# um982.net
KiCad netlist of a schematic drawn in Altium Designer
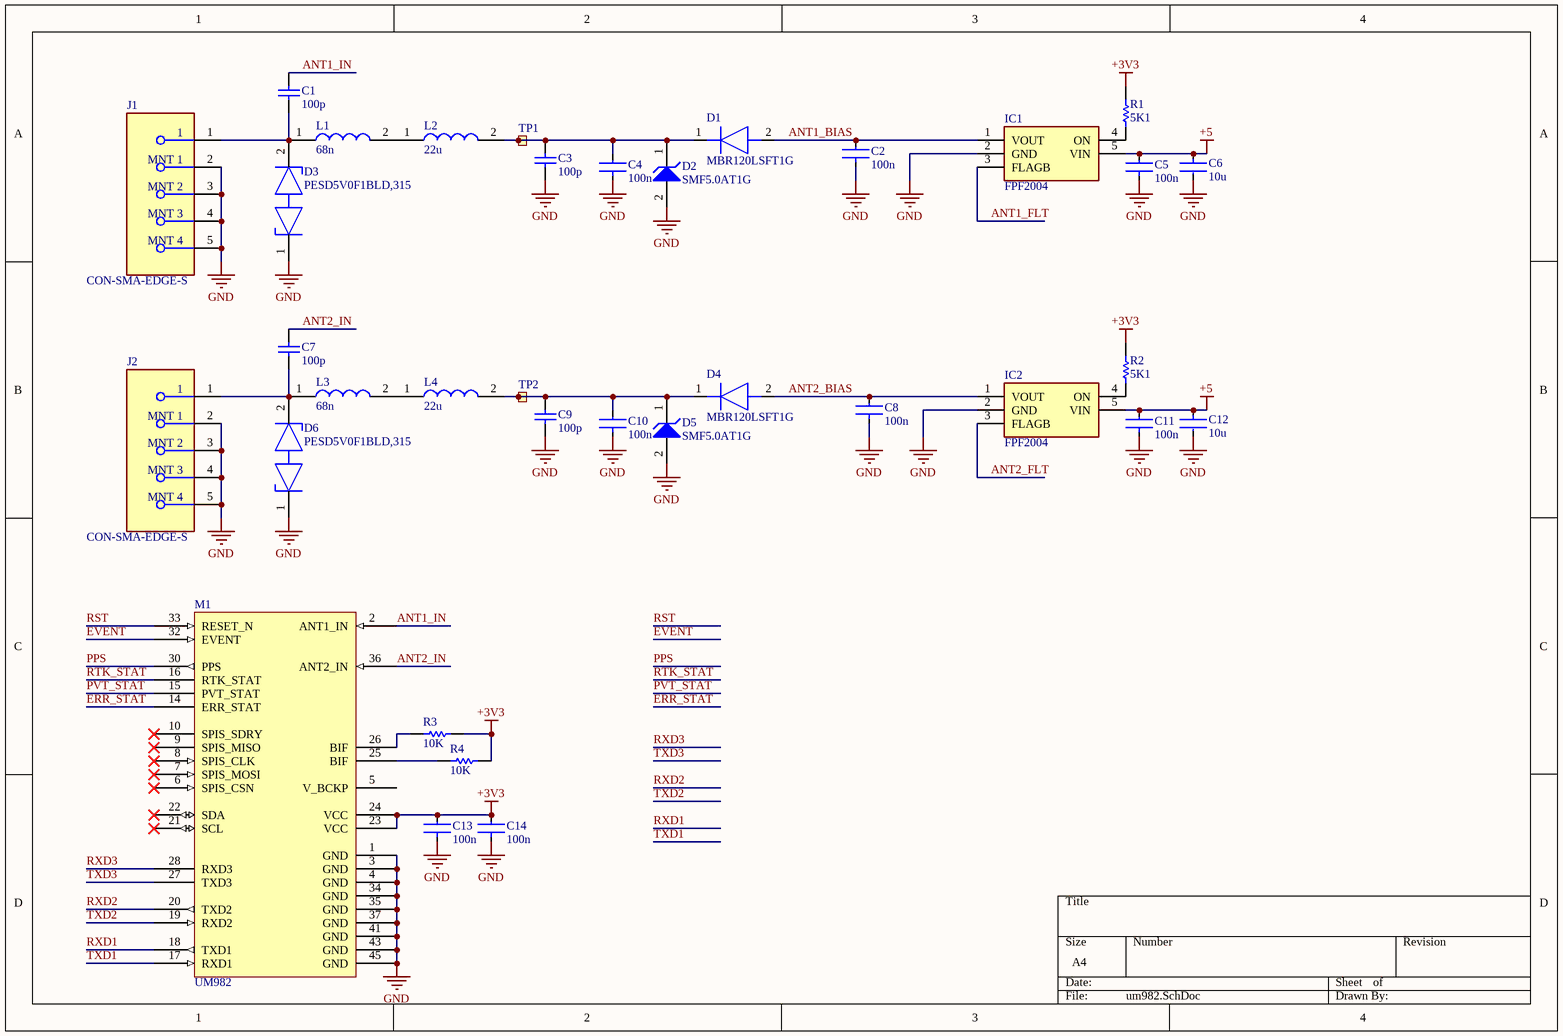
[diagram p0: um982.SchDoc]

(export (version "E")
  (design (tool "Eeschema 10.0.6"))
  (components
    (comp (ref "C1")
      (value "100p")
      (footprint "CAPC1005X55X25ML05T10")
      (fields (field (name "MANUFACTURER") "Murata") (field (name "PART NUMBER") "GRM1555C1H101JA01D"))
      (libsource (lib "Altium Content Vault") (part "CAP"))
    )
    (comp (ref "C2")
      (value "100n")
      (footprint "FP-C1005-050-0_05-IPC_C")
      (description "Multilayer Ceramic Capacitors 100nF ±10% 50V X7R SMD 0402")
      (fields (field (name "VOLTAGE") "50V") (field (name "TOLERANCE") "10%"))
      (libsource (lib "Altium Content Vault") (part "b4654b650e69147ec39a6b967a45e02"))
    )
    (comp (ref "C3")
      (value "100p")
      (footprint "CAPC1005X55X25ML05T10")
      (fields (field (name "MANUFACTURER") "Murata") (field (name "PART NUMBER") "GRM1555C1H101JA01D"))
      (libsource (lib "Altium Content Vault") (part "CAP"))
    )
    (comp (ref "C4")
      (value "100n")
      (footprint "FP-C1005-050-0_05-IPC_A")
      (description "Multilayer Ceramic Capacitors 100nF ±10% 50V X7R SMD 0402")
      (fields (field (name "VOLTAGE") "50V") (field (name "TOLERANCE") "10%"))
      (libsource (lib "Altium Content Vault") (part "b4654b650e69147ec39a6b967a45e02"))
    )
    (comp (ref "C5")
      (value "100n")
      (footprint "FP-C1005-050-0_05-IPC_C")
      (description "Multilayer Ceramic Capacitors 100nF ±10% 50V X7R SMD 0402")
      (fields (field (name "VOLTAGE") "50V") (field (name "TOLERANCE") "10%"))
      (libsource (lib "Altium Content Vault") (part "b4654b650e69147ec39a6b967a45e02"))
    )
    (comp (ref "C6")
      (value "10u")
      (footprint "FP-C1608-080-IPC_A")
      (description "CAP CER 10UF 25V X5R 0603")
      (fields (field (name "TOLERANCE") "20%") (field (name "Comment") "C1608X5R1E106M080AC"))
      (libsource (lib "Altium Content Vault") (part "11868f565c42a9108669ba33697ecf6"))
    )
    (comp (ref "C7")
      (value "100p")
      (footprint "CAPC1005X55X25ML05T10")
      (fields (field (name "MANUFACTURER") "Murata") (field (name "PART NUMBER") "GRM1555C1H101JA01D"))
      (libsource (lib "Altium Content Vault") (part "CAP"))
    )
    (comp (ref "C8")
      (value "100n")
      (footprint "FP-C1005-050-0_05-IPC_C")
      (description "Multilayer Ceramic Capacitors 100nF ±10% 50V X7R SMD 0402")
      (fields (field (name "VOLTAGE") "50V") (field (name "TOLERANCE") "10%"))
      (libsource (lib "Altium Content Vault") (part "b4654b650e69147ec39a6b967a45e02"))
    )
    (comp (ref "C9")
      (value "100p")
      (footprint "CAPC1005X55X25ML05T10")
      (fields (field (name "MANUFACTURER") "Murata") (field (name "PART NUMBER") "GRM1555C1H101JA01D"))
      (libsource (lib "Altium Content Vault") (part "CAP"))
    )
    (comp (ref "C10")
      (value "100n")
      (footprint "FP-C1005-050-0_05-IPC_A")
      (description "Multilayer Ceramic Capacitors 100nF ±10% 50V X7R SMD 0402")
      (fields (field (name "VOLTAGE") "50V") (field (name "TOLERANCE") "10%"))
      (libsource (lib "Altium Content Vault") (part "b4654b650e69147ec39a6b967a45e02"))
    )
    (comp (ref "C11")
      (value "100n")
      (footprint "FP-C1005-050-0_05-IPC_C")
      (description "Multilayer Ceramic Capacitors 100nF ±10% 50V X7R SMD 0402")
      (fields (field (name "VOLTAGE") "50V") (field (name "TOLERANCE") "10%"))
      (libsource (lib "Altium Content Vault") (part "b4654b650e69147ec39a6b967a45e02"))
    )
    (comp (ref "C12")
      (value "10u")
      (footprint "FP-C1608-080-IPC_A")
      (description "CAP CER 10UF 25V X5R 0603")
      (fields (field (name "TOLERANCE") "20%") (field (name "Comment") "C1608X5R1E106M080AC"))
      (libsource (lib "Altium Content Vault") (part "11868f565c42a9108669ba33697ecf6"))
    )
    (comp (ref "C13")
      (value "100n")
      (footprint "FP-C1005-050-0_05-IPC_A")
      (description "Multilayer Ceramic Capacitors 100nF ±10% 50V X7R SMD 0402")
      (fields (field (name "VOLTAGE") "50V") (field (name "TOLERANCE") "10%"))
      (libsource (lib "Altium Content Vault") (part "b4654b650e69147ec39a6b967a45e02"))
    )
    (comp (ref "C14")
      (value "100n")
      (footprint "FP-C1005-050-0_05-IPC_A")
      (description "Multilayer Ceramic Capacitors 100nF ±10% 50V X7R SMD 0402")
      (fields (field (name "VOLTAGE") "50V") (field (name "TOLERANCE") "10%"))
      (libsource (lib "Altium Content Vault") (part "b4654b650e69147ec39a6b967a45e02"))
    )
    (comp (ref "D1")
      (value "MBR120LSFT1G")
      (footprint "SamacSys:SODFL3616X98N")
      (description "Diode")
      (fields (field (name "MOUSER PART NUMBER") "863-MBR120LSFT1G"))
      (libsource (lib "*") (part "MBR120LSFT1G"))
    )
    (comp (ref "D2")
      (value "SMF5.0AT1G")
      (footprint "ONSC-SOD-123FL-2-498_V")
      (description "200 W Transient Voltage Suppressor, 2-Pin SOD-123FL, Pb-Free, Tape and Reel")
      (fields (field (name "MANUFACTURER") "On Semiconductor"))
      (libsource (lib "Altium Content Vault") (part "ONSC-K1A2-2"))
    )
    (comp (ref "D3")
      (value "PESD5V0F1BLD,315")
      (footprint "FP-SOD882D-MFG")
      (description "TVS DIODE 5.5V 15V 2DFN1006D")
      (libsource (lib "Altium Content Vault") (part "76a895bf0735dc68486ae99620ec8f1"))
    )
    (comp (ref "D4")
      (value "MBR120LSFT1G")
      (footprint "SamacSys:SODFL3616X98N")
      (description "Diode")
      (fields (field (name "MOUSER PART NUMBER") "863-MBR120LSFT1G"))
      (libsource (lib "*") (part "MBR120LSFT1G"))
    )
    (comp (ref "D5")
      (value "SMF5.0AT1G")
      (footprint "ONSC-SOD-123FL-2-498_V")
      (description "200 W Transient Voltage Suppressor, 2-Pin SOD-123FL, Pb-Free, Tape and Reel")
      (fields (field (name "MANUFACTURER") "On Semiconductor"))
      (libsource (lib "Altium Content Vault") (part "ONSC-K1A2-2"))
    )
    (comp (ref "D6")
      (value "PESD5V0F1BLD,315")
      (footprint "FP-SOD882D-MFG")
      (description "TVS DIODE 5.5V 15V 2DFN1006D")
      (libsource (lib "Altium Content Vault") (part "76a895bf0735dc68486ae99620ec8f1"))
    )
    (comp (ref "IC1")
      (value "FPF2004")
      (footprint "SamacSys:SOT65P210X110-5N")
      (description "Integrated Circuit")
      (fields (field (name "MOUSER PART NUMBER") "512-FPF2004"))
      (libsource (lib "*") (part "FPF2004"))
    )
    (comp (ref "IC2")
      (value "FPF2004")
      (footprint "SamacSys:SOT65P210X110-5N")
      (description "Integrated Circuit")
      (fields (field (name "MOUSER PART NUMBER") "512-FPF2004"))
      (libsource (lib "*") (part "FPF2004"))
    )
    (comp (ref "J1")
      (value "CON-SMA-EDGE-S")
      (footprint "FP-CON-SMA-EDGE-S-MFG")
      (description "CONN SMA JACK STR EDGE MNT")
      (fields
        (field (name "OCTOPART") "https://octopart.com/con-sma-edge-s-rf+solutions-70967450")
        (field (name "MANUFACTURER") "RF Solutions Ltd.")
      )
      (libsource (lib "Altium Content Vault") (part "a163d97a771fcdd2fd1f1a9264c171f"))
    )
    (comp (ref "J2")
      (value "CON-SMA-EDGE-S")
      (footprint "FP-CON-SMA-EDGE-S-MFG")
      (description "CONN SMA JACK STR EDGE MNT")
      (fields
        (field (name "OCTOPART") "https://octopart.com/con-sma-edge-s-rf+solutions-70967450")
        (field (name "MANUFACTURER") "RF Solutions Ltd.")
      )
      (libsource (lib "Altium Content Vault") (part "a163d97a771fcdd2fd1f1a9264c171f"))
    )
    (comp (ref "L1")
      (value "68n")
      (footprint "SamacSys:LQG15WH0N7B02D")
      (description "Inductor")
      (fields
        (field (name "MANUFACTURER_PART_NUMBER") "LQG15HS68NJ02D")
        (field (name "MOUSER PART NUMBER") "81-LQG15HS68NJ02D")
      )
      (libsource (lib "*") (part "LQG15HS68NJ02D"))
    )
    (comp (ref "L2")
      (value "22u")
      (footprint "SamacSys:INDM4532X340N")
      (description "Inductor")
      (fields
        (field (name "MANUFACTURER_PART_NUMBER") "NL453232T-220J-PF")
        (field (name "MOUSER PART NUMBER") "810-NL453232T-220JPF")
      )
      (libsource (lib "*") (part "NL453232T-220J-PF"))
    )
    (comp (ref "L3")
      (value "68n")
      (footprint "SamacSys:LQG15WH0N7B02D")
      (description "Inductor")
      (fields
        (field (name "MANUFACTURER_PART_NUMBER") "LQG15HS68NJ02D")
        (field (name "MOUSER PART NUMBER") "81-LQG15HS68NJ02D")
      )
      (libsource (lib "*") (part "LQG15HS68NJ02D"))
    )
    (comp (ref "L4")
      (value "22u")
      (footprint "SamacSys:INDM4532X340N")
      (description "Inductor")
      (fields
        (field (name "MANUFACTURER_PART_NUMBER") "NL453232T-220J-PF")
        (field (name "MOUSER PART NUMBER") "810-NL453232T-220JPF")
      )
      (libsource (lib "*") (part "NL453232T-220J-PF"))
    )
    (comp (ref "M1")
      (value "UM982")
      (footprint "UM982")
      (description "All-constellation Multi-frequencyHigh Precision Positioning & Heading Module")
      (libsource (lib "UM982") (part "UM982"))
    )
    (comp (ref "R1")
      (value "5K1")
      (footprint "RESC1005X40X25NL05T10")
      (fields (field (name "PART NUMBER") "RC0402FR-075K1L") (field (name "MANUFACTURER") "Yageo / Phycomp"))
      (libsource (lib "Altium Content Vault") (part "RES"))
    )
    (comp (ref "R2")
      (value "5K1")
      (footprint "RESC1005X40X25NL05T10")
      (fields (field (name "PART NUMBER") "RC0402FR-075K1L") (field (name "MANUFACTURER") "Yageo / Phycomp"))
      (libsource (lib "Altium Content Vault") (part "RES"))
    )
    (comp (ref "R3")
      (value "10K")
      (footprint "RESC1005X40X25LL05T10")
      (fields (field (name "PART NUMBER") "RC0402FR-0710KL") (field (name "MANUFACTURER") "Yageo / Phycomp"))
      (libsource (lib "Altium Content Vault") (part "RES"))
    )
    (comp (ref "R4")
      (value "10K")
      (footprint "RESC1005X40X25LL05T10")
      (fields (field (name "PART NUMBER") "RC0402FR-0710KL") (field (name "MANUFACTURER") "Yageo / Phycomp"))
      (libsource (lib "Altium Content Vault") (part "RES"))
    )
    (comp (ref "TP1")
      (value "Ø1.0mm,SMD")
      (footprint "TP_SMD_Ø1.0mm")
      (description "1.0mm circular SMD testpad")
      (fields
        (field (name "PART NUMBER") "TP_SMD_Ø1.0MM")
        (field (name "MANUFACTURER") "Nordic Semiconductor")
      )
      (libsource (lib "ParsaLibrary") (part "TP_SMD_Ø1.0MM"))
    )
    (comp (ref "TP2")
      (value "Ø1.0mm,SMD")
      (footprint "TP_SMD_Ø1.0mm")
      (description "1.0mm circular SMD testpad")
      (fields
        (field (name "PART NUMBER") "TP_SMD_Ø1.0MM")
        (field (name "MANUFACTURER") "Nordic Semiconductor")
      )
      (libsource (lib "ParsaLibrary") (part "TP_SMD_Ø1.0MM"))
    )
  )
  (nets
    (net (code "1") (name "+3V3") (class "Default")
      (node (ref "C13") (pin "2") (pinfunction "2_2") (pintype "passive"))
      (node (ref "C14") (pin "2") (pinfunction "2_2") (pintype "passive"))
      (node (ref "M1") (pin "23") (pinfunction "VCC_23") (pintype "power_in"))
      (node (ref "M1") (pin "24") (pinfunction "VCC_24") (pintype "power_in"))
      (node (ref "R1") (pin "1") (pinfunction "1_1") (pintype "passive"))
      (node (ref "R2") (pin "1") (pinfunction "1_1") (pintype "passive"))
      (node (ref "R3") (pin "1") (pinfunction "1_1") (pintype "passive"))
      (node (ref "R4") (pin "1") (pinfunction "1_1") (pintype "passive"))
    )
    (net (code "2") (name "+5") (class "Default")
      (node (ref "C11") (pin "2") (pinfunction "2_2") (pintype "passive"))
      (node (ref "C12") (pin "1") (pinfunction "1_1") (pintype "passive"))
      (node (ref "C5") (pin "2") (pinfunction "2_2") (pintype "passive"))
      (node (ref "C6") (pin "1") (pinfunction "1_1") (pintype "passive"))
      (node (ref "IC1") (pin "5") (pinfunction "VIN_5") (pintype "passive"))
      (node (ref "IC2") (pin "5") (pinfunction "VIN_5") (pintype "passive"))
    )
    (net (code "3") (name "/ANT1_BIAS") (class "Default")
      (node (ref "C2") (pin "2") (pinfunction "2_2") (pintype "passive"))
      (node (ref "D1") (pin "2") (pinfunction "A_2") (pintype "passive"))
      (node (ref "IC1") (pin "1") (pinfunction "VOUT_1") (pintype "passive"))
    )
    (net (code "4") (name "/ANT1_FLT") (class "Default")
      (node (ref "IC1") (pin "3") (pinfunction "FLAGB_3") (pintype "passive"))
    )
    (net (code "5") (name "/ANT1_IN") (class "Default")
      (node (ref "C1") (pin "2") (pinfunction "2_2") (pintype "passive"))
      (node (ref "M1") (pin "2") (pinfunction "ANT1_IN_2") (pintype "input"))
    )
    (net (code "6") (name "/ANT2_BIAS") (class "Default")
      (node (ref "C8") (pin "2") (pinfunction "2_2") (pintype "passive"))
      (node (ref "D4") (pin "2") (pinfunction "A_2") (pintype "passive"))
      (node (ref "IC2") (pin "1") (pinfunction "VOUT_1") (pintype "passive"))
    )
    (net (code "7") (name "/ANT2_FLT") (class "Default")
      (node (ref "IC2") (pin "3") (pinfunction "FLAGB_3") (pintype "passive"))
    )
    (net (code "8") (name "/ANT2_IN") (class "Default")
      (node (ref "C7") (pin "2") (pinfunction "2_2") (pintype "passive"))
      (node (ref "M1") (pin "36") (pinfunction "ANT2_IN_36") (pintype "input"))
    )
    (net (code "9") (name "/ERR_STAT") (class "Default")
      (node (ref "M1") (pin "14") (pinfunction "ERR_STAT_14") (pintype "passive"))
    )
    (net (code "10") (name "/EVENT") (class "Default")
      (node (ref "M1") (pin "32") (pinfunction "EVENT_32") (pintype "input"))
    )
    (net (code "11") (name "/PPS") (class "Default")
      (node (ref "M1") (pin "30") (pinfunction "PPS_30") (pintype "output"))
    )
    (net (code "12") (name "/PVT_STAT") (class "Default")
      (node (ref "M1") (pin "15") (pinfunction "PVT_STAT_15") (pintype "passive"))
    )
    (net (code "13") (name "/RST") (class "Default")
      (node (ref "M1") (pin "33") (pinfunction "RESET_N_33") (pintype "input"))
    )
    (net (code "14") (name "/RTK_STAT") (class "Default")
      (node (ref "M1") (pin "16") (pinfunction "RTK_STAT_16") (pintype "passive"))
    )
    (net (code "15") (name "/RXD1") (class "Default")
      (node (ref "M1") (pin "18") (pinfunction "TXD1_18") (pintype "output"))
    )
    (net (code "16") (name "/RXD2") (class "Default")
      (node (ref "M1") (pin "20") (pinfunction "TXD2_20") (pintype "output"))
    )
    (net (code "17") (name "/RXD3") (class "Default")
      (node (ref "M1") (pin "28") (pinfunction "RXD3_28") (pintype "passive"))
    )
    (net (code "18") (name "/TXD1") (class "Default")
      (node (ref "M1") (pin "17") (pinfunction "RXD1_17") (pintype "input"))
    )
    (net (code "19") (name "/TXD2") (class "Default")
      (node (ref "M1") (pin "19") (pinfunction "RXD2_19") (pintype "input"))
    )
    (net (code "20") (name "/TXD3") (class "Default")
      (node (ref "M1") (pin "27") (pinfunction "TXD3_27") (pintype "passive"))
    )
    (net (code "21") (name "GND") (class "Default")
      (node (ref "C10") (pin "1") (pinfunction "1_1") (pintype "passive"))
      (node (ref "C11") (pin "1") (pinfunction "1_1") (pintype "passive"))
      (node (ref "C12") (pin "2") (pinfunction "2_2") (pintype "passive"))
      (node (ref "C13") (pin "1") (pinfunction "1_1") (pintype "passive"))
      (node (ref "C14") (pin "1") (pinfunction "1_1") (pintype "passive"))
      (node (ref "C2") (pin "1") (pinfunction "1_1") (pintype "passive"))
      (node (ref "C3") (pin "2") (pinfunction "2_2") (pintype "passive"))
      (node (ref "C4") (pin "1") (pinfunction "1_1") (pintype "passive"))
      (node (ref "C5") (pin "1") (pinfunction "1_1") (pintype "passive"))
      (node (ref "C6") (pin "2") (pinfunction "2_2") (pintype "passive"))
      (node (ref "C8") (pin "1") (pinfunction "1_1") (pintype "passive"))
      (node (ref "C9") (pin "2") (pinfunction "2_2") (pintype "passive"))
      (node (ref "D2") (pin "2") (pinfunction "A_2") (pintype "passive"))
      (node (ref "D3") (pin "1") (pinfunction "cathode(diode_1)_1") (pintype "passive"))
      (node (ref "D5") (pin "2") (pinfunction "A_2") (pintype "passive"))
      (node (ref "D6") (pin "1") (pinfunction "cathode(diode_1)_1") (pintype "passive"))
      (node (ref "IC1") (pin "2") (pinfunction "GND_2") (pintype "passive"))
      (node (ref "IC2") (pin "2") (pinfunction "GND_2") (pintype "passive"))
      (node (ref "J1") (pin "2") (pinfunction "MNT_1_2") (pintype "passive"))
      (node (ref "J1") (pin "3") (pinfunction "MNT_2_3") (pintype "passive"))
      (node (ref "J1") (pin "4") (pinfunction "MNT_3_4") (pintype "passive"))
      (node (ref "J1") (pin "5") (pinfunction "MNT_4_5") (pintype "passive"))
      (node (ref "J2") (pin "2") (pinfunction "MNT_1_2") (pintype "passive"))
      (node (ref "J2") (pin "3") (pinfunction "MNT_2_3") (pintype "passive"))
      (node (ref "J2") (pin "4") (pinfunction "MNT_3_4") (pintype "passive"))
      (node (ref "J2") (pin "5") (pinfunction "MNT_4_5") (pintype "passive"))
      (node (ref "M1") (pin "1") (pinfunction "GND_1") (pintype "passive"))
      (node (ref "M1") (pin "3") (pinfunction "GND_3") (pintype "passive"))
      (node (ref "M1") (pin "34") (pinfunction "GND_34") (pintype "passive"))
      (node (ref "M1") (pin "35") (pinfunction "GND_35") (pintype "passive"))
      (node (ref "M1") (pin "37") (pinfunction "GND_37") (pintype "passive"))
      (node (ref "M1") (pin "4") (pinfunction "GND_4") (pintype "passive"))
      (node (ref "M1") (pin "41") (pinfunction "GND_41") (pintype "passive"))
      (node (ref "M1") (pin "43") (pinfunction "GND_43") (pintype "passive"))
      (node (ref "M1") (pin "45") (pinfunction "GND_45") (pintype "passive"))
    )
    (net (code "22") (name "Net-(D1-K)") (class "Default")
      (node (ref "C3") (pin "1") (pinfunction "1_1") (pintype "passive"))
      (node (ref "C4") (pin "2") (pinfunction "2_2") (pintype "passive"))
      (node (ref "D1") (pin "1") (pinfunction "K_1") (pintype "passive"))
      (node (ref "D2") (pin "1") (pinfunction "K_1") (pintype "passive"))
      (node (ref "L2") (pin "2") (pinfunction "2_2") (pintype "passive"))
      (node (ref "TP1") (pin "1") (pinfunction "1_1") (pintype "passive"))
    )
    (net (code "23") (name "Net-(D3-cathode(diode_2))") (class "Default")
      (node (ref "C1") (pin "1") (pinfunction "1_1") (pintype "passive"))
      (node (ref "D3") (pin "2") (pinfunction "cathode(diode_2)_2") (pintype "passive"))
      (node (ref "J1") (pin "1") (pinfunction "1_1") (pintype "passive"))
      (node (ref "L1") (pin "1") (pinfunction "1_1") (pintype "passive"))
    )
    (net (code "24") (name "Net-(D4-K)") (class "Default")
      (node (ref "C10") (pin "2") (pinfunction "2_2") (pintype "passive"))
      (node (ref "C9") (pin "1") (pinfunction "1_1") (pintype "passive"))
      (node (ref "D4") (pin "1") (pinfunction "K_1") (pintype "passive"))
      (node (ref "D5") (pin "1") (pinfunction "K_1") (pintype "passive"))
      (node (ref "L4") (pin "2") (pinfunction "2_2") (pintype "passive"))
      (node (ref "TP2") (pin "1") (pinfunction "1_1") (pintype "passive"))
    )
    (net (code "25") (name "Net-(D6-cathode(diode_2))") (class "Default")
      (node (ref "C7") (pin "1") (pinfunction "1_1") (pintype "passive"))
      (node (ref "D6") (pin "2") (pinfunction "cathode(diode_2)_2") (pintype "passive"))
      (node (ref "J2") (pin "1") (pinfunction "1_1") (pintype "passive"))
      (node (ref "L3") (pin "1") (pinfunction "1_1") (pintype "passive"))
    )
    (net (code "26") (name "Net-(IC1-ON)") (class "Default")
      (node (ref "IC1") (pin "4") (pinfunction "ON_4") (pintype "passive"))
      (node (ref "R1") (pin "2") (pinfunction "2_2") (pintype "passive"))
    )
    (net (code "27") (name "Net-(IC2-ON)") (class "Default")
      (node (ref "IC2") (pin "4") (pinfunction "ON_4") (pintype "passive"))
      (node (ref "R2") (pin "2") (pinfunction "2_2") (pintype "passive"))
    )
    (net (code "28") (name "Net-(L1-Pad2)") (class "Default")
      (node (ref "L1") (pin "2") (pinfunction "2_2") (pintype "passive"))
      (node (ref "L2") (pin "1") (pinfunction "1_1") (pintype "passive"))
    )
    (net (code "29") (name "Net-(L3-Pad2)") (class "Default")
      (node (ref "L3") (pin "2") (pinfunction "2_2") (pintype "passive"))
      (node (ref "L4") (pin "1") (pinfunction "1_1") (pintype "passive"))
    )
    (net (code "30") (name "Net-(M1-BIF-Pad25)") (class "Default")
      (node (ref "M1") (pin "25") (pinfunction "BIF_25") (pintype "passive"))
      (node (ref "R4") (pin "2") (pinfunction "2_2") (pintype "passive"))
    )
    (net (code "31") (name "Net-(M1-BIF-Pad26)") (class "Default")
      (node (ref "M1") (pin "26") (pinfunction "BIF_26") (pintype "passive"))
      (node (ref "R3") (pin "2") (pinfunction "2_2") (pintype "passive"))
    )
    (net (code "32") (name "unconnected-(M1-SCL-Pad21)") (class "Default")
      (node (ref "M1") (pin "21") (pinfunction "SCL_21") (pintype "bidirectional+no_connect"))
    )
    (net (code "33") (name "unconnected-(M1-SDA-Pad22)") (class "Default")
      (node (ref "M1") (pin "22") (pinfunction "SDA_22") (pintype "bidirectional+no_connect"))
    )
    (net (code "34") (name "unconnected-(M1-SPIS_CLK-Pad8)") (class "Default")
      (node (ref "M1") (pin "8") (pinfunction "SPIS_CLK_8") (pintype "input+no_connect"))
    )
    (net (code "35") (name "unconnected-(M1-SPIS_CSN-Pad6)") (class "Default")
      (node (ref "M1") (pin "6") (pinfunction "SPIS_CSN_6") (pintype "input+no_connect"))
    )
    (net (code "36") (name "unconnected-(M1-SPIS_MISO-Pad9)") (class "Default")
      (node (ref "M1") (pin "9") (pinfunction "SPIS_MISO_9") (pintype "passive+no_connect"))
    )
    (net (code "37") (name "unconnected-(M1-SPIS_MOSI-Pad7)") (class "Default")
      (node (ref "M1") (pin "7") (pinfunction "SPIS_MOSI_7") (pintype "input+no_connect"))
    )
    (net (code "38") (name "unconnected-(M1-SPIS_SDRY-Pad10)") (class "Default")
      (node (ref "M1") (pin "10") (pinfunction "SPIS_SDRY_10") (pintype "passive+no_connect"))
    )
    (net (code "39") (name "unconnected-(M1-V_BCKP-Pad5)") (class "Default")
      (node (ref "M1") (pin "5") (pinfunction "V_BCKP_5") (pintype "passive"))
    )
  )
)
